# Pure_VCA_SMD_V2_2.net
KiCad netlist of a schematic drawn in EAGLE
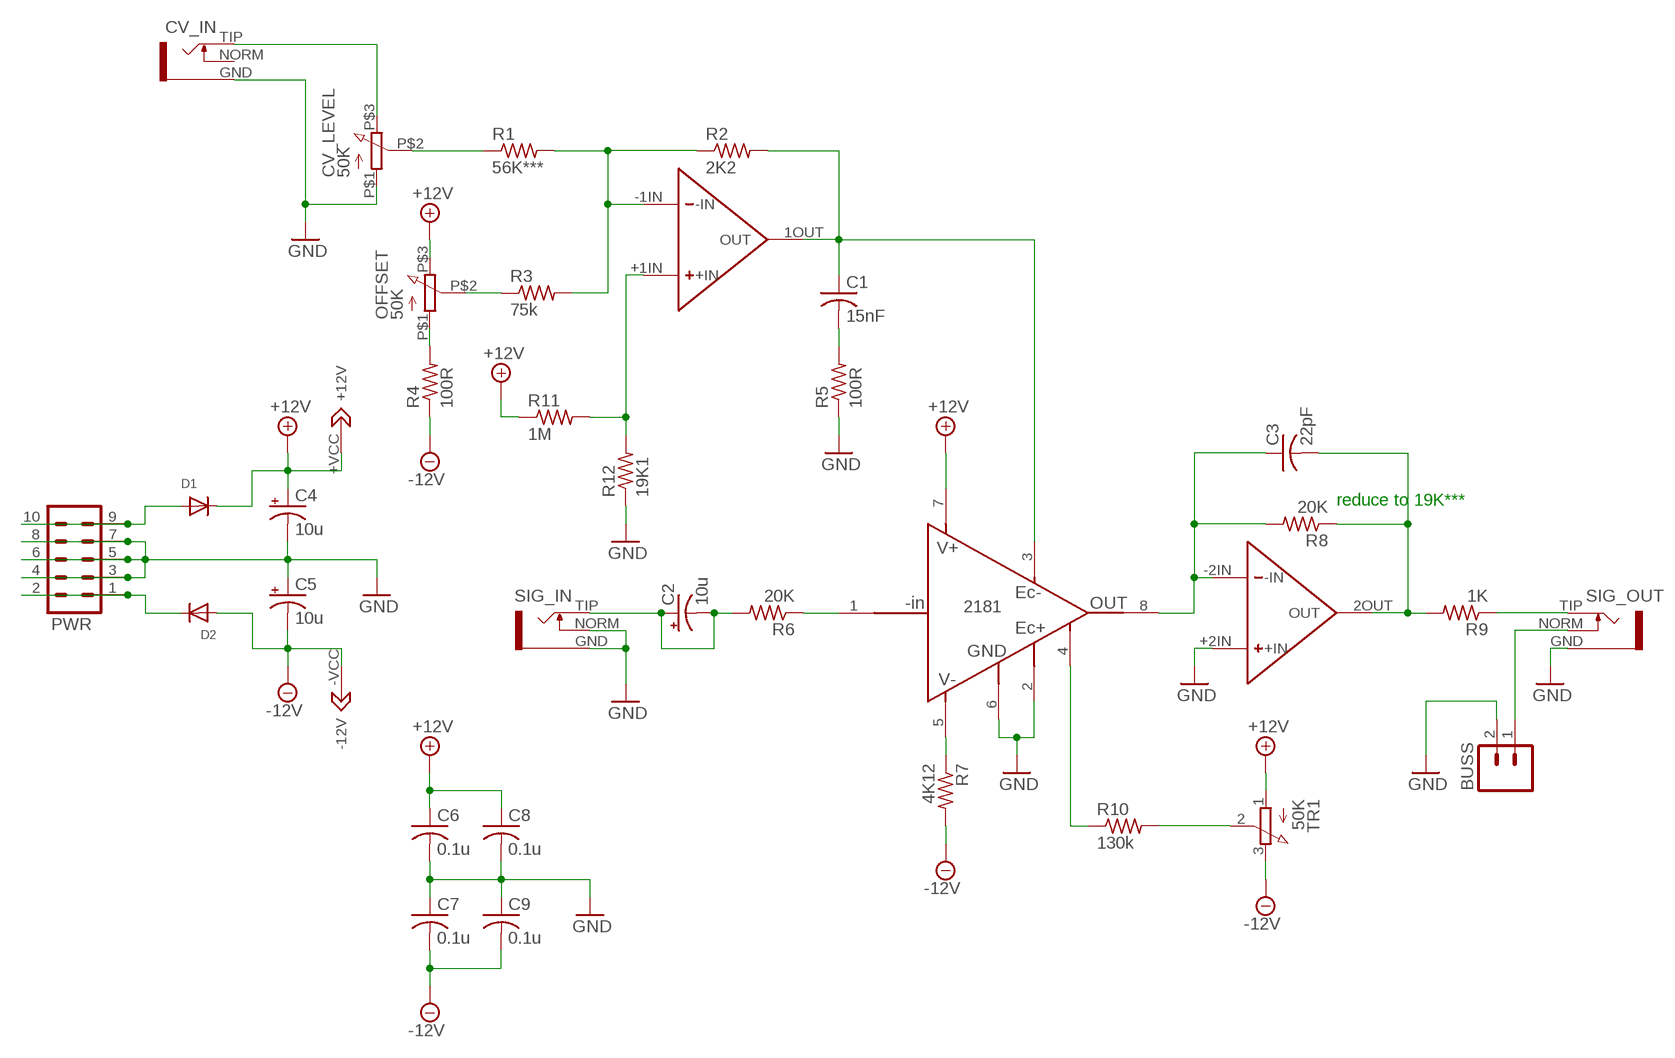
[diagram p0: schematic, sheet 1]

(export (version "E")
  (design (tool "Eeschema 10.0.6"))
  (components
    (comp (ref "BUSS")
      (value "M02PTH")
      (footprint "eagle-import:1X02")
      (libsource (lib "eagle-import") (part "M02PTH"))
    )
    (comp (ref "C1")
      (value "15nF")
      (footprint "eagle-import:C0805K")
      (libsource (lib "eagle-import") (part "C-USC0805K"))
    )
    (comp (ref "C2")
      (value "10u")
      (footprint "eagle-import:153CLV-0505")
      (libsource (lib "eagle-import") (part "CPOL-US153CLV-0505"))
    )
    (comp (ref "C3")
      (value "22pF")
      (footprint "eagle-import:C0805K")
      (libsource (lib "eagle-import") (part "C-USC0805K"))
    )
    (comp (ref "C4")
      (value "10u")
      (footprint "eagle-import:153CLV-0505")
      (libsource (lib "eagle-import") (part "CPOL-US153CLV-0505"))
    )
    (comp (ref "C5")
      (value "10u")
      (footprint "eagle-import:153CLV-0505")
      (libsource (lib "eagle-import") (part "CPOL-US153CLV-0505"))
    )
    (comp (ref "C6")
      (value "0.1u")
      (footprint "eagle-import:C0805K")
      (libsource (lib "eagle-import") (part "C-USC0805K"))
    )
    (comp (ref "C7")
      (value "0.1u")
      (footprint "eagle-import:C0805K")
      (libsource (lib "eagle-import") (part "C-USC0805K"))
    )
    (comp (ref "C8")
      (value "0.1u")
      (footprint "eagle-import:C0805K")
      (libsource (lib "eagle-import") (part "C-USC0805K"))
    )
    (comp (ref "C9")
      (value "0.1u")
      (footprint "eagle-import:C0805K")
      (libsource (lib "eagle-import") (part "C-USC0805K"))
    )
    (comp (ref "CV_IN")
      (value "S_JACK")
      (footprint "eagle-import:S_JACK")
      (libsource (lib "eagle-import") (part "S_JACK"))
    )
    (comp (ref "CV_LEVEL")
      (value "50K")
      (footprint "eagle-import:Q-POT")
      (libsource (lib "eagle-import") (part "Q-POT"))
    )
    (comp (ref "D1")
      (value "DIODESMA")
      (footprint "eagle-import:SMADIODE")
      (libsource (lib "eagle-import") (part "DIODESMA"))
    )
    (comp (ref "D2")
      (value "DIODESMA")
      (footprint "eagle-import:SMADIODE")
      (libsource (lib "eagle-import") (part "DIODESMA"))
    )
    (comp (ref "OFFSET")
      (value "50K")
      (footprint "eagle-import:Q-POT")
      (libsource (lib "eagle-import") (part "Q-POT"))
    )
    (comp (ref "PWR")
      (value "M05X2SHD")
      (footprint "eagle-import:2X5-SHROUDED")
      (libsource (lib "eagle-import") (part "M05X2SHD"))
    )
    (comp (ref "R1")
      (value "56K***")
      (footprint "eagle-import:R0805")
      (libsource (lib "eagle-import") (part "R-US_R0805"))
    )
    (comp (ref "R2")
      (value "2K2")
      (footprint "eagle-import:R0805")
      (libsource (lib "eagle-import") (part "R-US_R0805"))
    )
    (comp (ref "R3")
      (value "75k")
      (footprint "eagle-import:R0805")
      (libsource (lib "eagle-import") (part "R-US_R0805"))
    )
    (comp (ref "R4")
      (value "100R")
      (footprint "eagle-import:R0805")
      (libsource (lib "eagle-import") (part "R-US_R0805"))
    )
    (comp (ref "R5")
      (value "100R")
      (footprint "eagle-import:R0805")
      (libsource (lib "eagle-import") (part "R-US_R0805"))
    )
    (comp (ref "R6")
      (value "20K")
      (footprint "eagle-import:R0805")
      (libsource (lib "eagle-import") (part "R-US_R0805"))
    )
    (comp (ref "R7")
      (value "4K12")
      (footprint "eagle-import:R0805")
      (libsource (lib "eagle-import") (part "R-US_R0805"))
    )
    (comp (ref "R8")
      (value "20K")
      (footprint "eagle-import:R0805")
      (libsource (lib "eagle-import") (part "R-US_R0805"))
    )
    (comp (ref "R9")
      (value "1K")
      (footprint "eagle-import:R0805")
      (libsource (lib "eagle-import") (part "R-US_R0805"))
    )
    (comp (ref "R10")
      (value "130k")
      (footprint "eagle-import:R0805")
      (libsource (lib "eagle-import") (part "R-US_R0805"))
    )
    (comp (ref "R11")
      (value "1M")
      (footprint "eagle-import:R0805")
      (libsource (lib "eagle-import") (part "R-US_R0805"))
    )
    (comp (ref "R12")
      (value "19K1")
      (footprint "eagle-import:R0805")
      (libsource (lib "eagle-import") (part "R-US_R0805"))
    )
    (comp (ref "SIG_IN")
      (value "S_JACK")
      (footprint "eagle-import:S_JACK")
      (libsource (lib "eagle-import") (part "S_JACK"))
    )
    (comp (ref "SIG_OUT")
      (value "S_JACK")
      (footprint "eagle-import:S_JACK")
      (libsource (lib "eagle-import") (part "S_JACK"))
    )
    (comp (ref "TR1")
      (value "50K")
      (footprint "eagle-import:TRIM_3269W")
      (libsource (lib "eagle-import") (part "TRIM_3269W"))
    )
    (comp (ref "U1")
      (value "DUAL_OPAMP")
      (footprint "eagle-import:DUAL_OPAMP")
      (libsource (lib "eagle-import") (part "DUAL_OPAMP"))
    )
    (comp (ref "U2")
      (value "THAT_2181_SMD")
      (footprint "eagle-import:SOIC--8")
      (libsource (lib "eagle-import") (part "THAT_2181_SMD"))
    )
  )
  (nets
    (net (code "1") (name "+12V") (class "Default")
      (node (ref "C4") (pin "+") (pinfunction "+_+") (pintype "passive"))
      (node (ref "C6") (pin "1") (pinfunction "1_1") (pintype "passive"))
      (node (ref "C8") (pin "1") (pinfunction "1_1") (pintype "passive"))
      (node (ref "D1") (pin "C") (pinfunction "C_C") (pintype "passive"))
      (node (ref "OFFSET") (pin "P$3") (pinfunction "3_P$3") (pintype "passive"))
      (node (ref "R11") (pin "1") (pinfunction "1_1") (pintype "passive"))
      (node (ref "TR1") (pin "1") (pinfunction "1_1") (pintype "passive"))
      (node (ref "U1") (pin "+VCC") (pinfunction "+12V_+VCC") (pintype "bidirectional"))
      (node (ref "U2") (pin "7") (pinfunction "V+_7") (pintype "bidirectional"))
    )
    (net (code "2") (name "-12V") (class "Default")
      (node (ref "C5") (pin "-") (pinfunction "-_-") (pintype "passive"))
      (node (ref "C7") (pin "2") (pinfunction "2_2") (pintype "passive"))
      (node (ref "C9") (pin "2") (pinfunction "2_2") (pintype "passive"))
      (node (ref "D2") (pin "A") (pinfunction "A_A") (pintype "passive"))
      (node (ref "R4") (pin "1") (pinfunction "1_1") (pintype "passive"))
      (node (ref "R7") (pin "2") (pinfunction "2_2") (pintype "passive"))
      (node (ref "TR1") (pin "3") (pinfunction "3_3") (pintype "passive"))
      (node (ref "U1") (pin "-VCC") (pinfunction "-12V_-VCC") (pintype "bidirectional"))
    )
    (net (code "3") (name "GND") (class "Default")
      (node (ref "BUSS") (pin "2") (pinfunction "2_2") (pintype "passive"))
      (node (ref "C4") (pin "-") (pinfunction "-_-") (pintype "passive"))
      (node (ref "C5") (pin "+") (pinfunction "+_+") (pintype "passive"))
      (node (ref "C6") (pin "2") (pinfunction "2_2") (pintype "passive"))
      (node (ref "C7") (pin "1") (pinfunction "1_1") (pintype "passive"))
      (node (ref "C8") (pin "2") (pinfunction "2_2") (pintype "passive"))
      (node (ref "C9") (pin "1") (pinfunction "1_1") (pintype "passive"))
      (node (ref "CV_IN") (pin "GND") (pinfunction "GND_GND") (pintype "passive"))
      (node (ref "CV_LEVEL") (pin "P$1") (pinfunction "1_P$1") (pintype "passive"))
      (node (ref "PWR") (pin "3") (pinfunction "3_3") (pintype "passive"))
      (node (ref "PWR") (pin "4") (pinfunction "4_4") (pintype "passive"))
      (node (ref "PWR") (pin "5") (pinfunction "5_5") (pintype "passive"))
      (node (ref "PWR") (pin "6") (pinfunction "6_6") (pintype "passive"))
      (node (ref "PWR") (pin "7") (pinfunction "7_7") (pintype "passive"))
      (node (ref "PWR") (pin "8") (pinfunction "8_8") (pintype "passive"))
      (node (ref "R12") (pin "1") (pinfunction "1_1") (pintype "passive"))
      (node (ref "R5") (pin "1") (pinfunction "1_1") (pintype "passive"))
      (node (ref "SIG_IN") (pin "GND") (pinfunction "GND_GND") (pintype "passive"))
      (node (ref "SIG_IN") (pin "NORM") (pinfunction "NORM_NORM") (pintype "passive"))
      (node (ref "SIG_OUT") (pin "GND") (pinfunction "GND_GND") (pintype "passive"))
      (node (ref "U1") (pin "+2IN") (pinfunction "+IN_+2IN") (pintype "bidirectional"))
      (node (ref "U2") (pin "2") (pinfunction "EC+_2") (pintype "bidirectional"))
      (node (ref "U2") (pin "6") (pinfunction "GND_6") (pintype "bidirectional"))
    )
    (net (code "4") (name "Net-(BUSS-Pad1)") (class "Default")
      (node (ref "BUSS") (pin "1") (pinfunction "1_1") (pintype "passive"))
      (node (ref "SIG_OUT") (pin "NORM") (pinfunction "NORM_NORM") (pintype "passive"))
    )
    (net (code "5") (name "Net-(C1-Pad2)") (class "Default")
      (node (ref "C1") (pin "2") (pinfunction "2_2") (pintype "passive"))
      (node (ref "R5") (pin "2") (pinfunction "2_2") (pintype "passive"))
    )
    (net (code "6") (name "Net-(C2-Pad+)") (class "Default")
      (node (ref "C2") (pin "+") (pinfunction "+_+") (pintype "passive"))
      (node (ref "C2") (pin "-") (pinfunction "-_-") (pintype "passive"))
      (node (ref "R6") (pin "2") (pinfunction "2_2") (pintype "passive"))
      (node (ref "SIG_IN") (pin "TIP") (pinfunction "TIP_TIP") (pintype "passive"))
    )
    (net (code "7") (name "Net-(CV_LEVEL-2)") (class "Default")
      (node (ref "CV_LEVEL") (pin "P$2") (pinfunction "2_P$2") (pintype "passive"))
      (node (ref "R1") (pin "1") (pinfunction "1_1") (pintype "passive"))
    )
    (net (code "8") (name "Net-(CV_LEVEL-3)") (class "Default")
      (node (ref "CV_IN") (pin "TIP") (pinfunction "TIP_TIP") (pintype "passive"))
      (node (ref "CV_LEVEL") (pin "P$3") (pinfunction "3_P$3") (pintype "passive"))
    )
    (net (code "9") (name "Net-(D1-PadA)") (class "Default")
      (node (ref "D1") (pin "A") (pinfunction "A_A") (pintype "passive"))
      (node (ref "PWR") (pin "10") (pinfunction "10_10") (pintype "passive"))
      (node (ref "PWR") (pin "9") (pinfunction "9_9") (pintype "passive"))
    )
    (net (code "10") (name "Net-(D2-PadC)") (class "Default")
      (node (ref "D2") (pin "C") (pinfunction "C_C") (pintype "passive"))
      (node (ref "PWR") (pin "1") (pinfunction "1_1") (pintype "passive"))
      (node (ref "PWR") (pin "2") (pinfunction "2_2") (pintype "passive"))
    )
    (net (code "11") (name "Net-(OFFSET-1)") (class "Default")
      (node (ref "OFFSET") (pin "P$1") (pinfunction "1_P$1") (pintype "passive"))
      (node (ref "R4") (pin "2") (pinfunction "2_2") (pintype "passive"))
    )
    (net (code "12") (name "Net-(OFFSET-2)") (class "Default")
      (node (ref "OFFSET") (pin "P$2") (pinfunction "2_P$2") (pintype "passive"))
      (node (ref "R3") (pin "1") (pinfunction "1_1") (pintype "passive"))
    )
    (net (code "13") (name "Net-(R9-Pad1)") (class "Default")
      (node (ref "R9") (pin "1") (pinfunction "1_1") (pintype "passive"))
      (node (ref "SIG_OUT") (pin "TIP") (pinfunction "TIP_TIP") (pintype "passive"))
    )
    (net (code "14") (name "Net-(R10-Pad2)") (class "Default")
      (node (ref "R10") (pin "2") (pinfunction "2_2") (pintype "passive"))
      (node (ref "TR1") (pin "2") (pinfunction "2_2") (pintype "passive"))
    )
    (net (code "15") (name "Net-(U1A-+IN)") (class "Default")
      (node (ref "R11") (pin "2") (pinfunction "2_2") (pintype "passive"))
      (node (ref "R12") (pin "2") (pinfunction "2_2") (pintype "passive"))
      (node (ref "U1") (pin "+1IN") (pinfunction "+IN_+1IN") (pintype "bidirectional"))
    )
    (net (code "16") (name "Net-(U1A--IN)") (class "Default")
      (node (ref "R1") (pin "2") (pinfunction "2_2") (pintype "passive"))
      (node (ref "R2") (pin "1") (pinfunction "1_1") (pintype "passive"))
      (node (ref "R3") (pin "2") (pinfunction "2_2") (pintype "passive"))
      (node (ref "U1") (pin "-1IN") (pinfunction "-IN_-1IN") (pintype "bidirectional"))
    )
    (net (code "17") (name "Net-(U1A-OUT)") (class "Default")
      (node (ref "C1") (pin "1") (pinfunction "1_1") (pintype "passive"))
      (node (ref "R2") (pin "2") (pinfunction "2_2") (pintype "passive"))
      (node (ref "U1") (pin "1OUT") (pinfunction "OUT_1OUT") (pintype "bidirectional"))
      (node (ref "U2") (pin "3") (pinfunction "EC-_3") (pintype "bidirectional"))
    )
    (net (code "18") (name "Net-(U1B--IN)") (class "Default")
      (node (ref "C3") (pin "1") (pinfunction "1_1") (pintype "passive"))
      (node (ref "R8") (pin "2") (pinfunction "2_2") (pintype "passive"))
      (node (ref "U1") (pin "-2IN") (pinfunction "-IN_-2IN") (pintype "bidirectional"))
      (node (ref "U2") (pin "8") (pinfunction "OUT_8") (pintype "bidirectional"))
    )
    (net (code "19") (name "Net-(U1B-OUT)") (class "Default")
      (node (ref "C3") (pin "2") (pinfunction "2_2") (pintype "passive"))
      (node (ref "R8") (pin "1") (pinfunction "1_1") (pintype "passive"))
      (node (ref "R9") (pin "2") (pinfunction "2_2") (pintype "passive"))
      (node (ref "U1") (pin "2OUT") (pinfunction "OUT_2OUT") (pintype "bidirectional"))
    )
    (net (code "20") (name "Net-(U2--IN)") (class "Default")
      (node (ref "R6") (pin "1") (pinfunction "1_1") (pintype "passive"))
      (node (ref "U2") (pin "1") (pinfunction "-IN_1") (pintype "bidirectional"))
    )
    (net (code "21") (name "Net-(U2-SYM)") (class "Default")
      (node (ref "R10") (pin "1") (pinfunction "1_1") (pintype "passive"))
      (node (ref "U2") (pin "4") (pinfunction "SYM_4") (pintype "bidirectional"))
    )
    (net (code "22") (name "Net-(U2-V-)") (class "Default")
      (node (ref "R7") (pin "1") (pinfunction "1_1") (pintype "passive"))
      (node (ref "U2") (pin "5") (pinfunction "V-_5") (pintype "bidirectional"))
    )
    (net (code "23") (name "unconnected-(CV_IN-PadNORM)") (class "Default")
      (node (ref "CV_IN") (pin "NORM") (pinfunction "NORM_NORM") (pintype "passive"))
    )
  )
)
